# TV-B-Gone.net
KiCad netlist of a schematic drawn in EAGLE
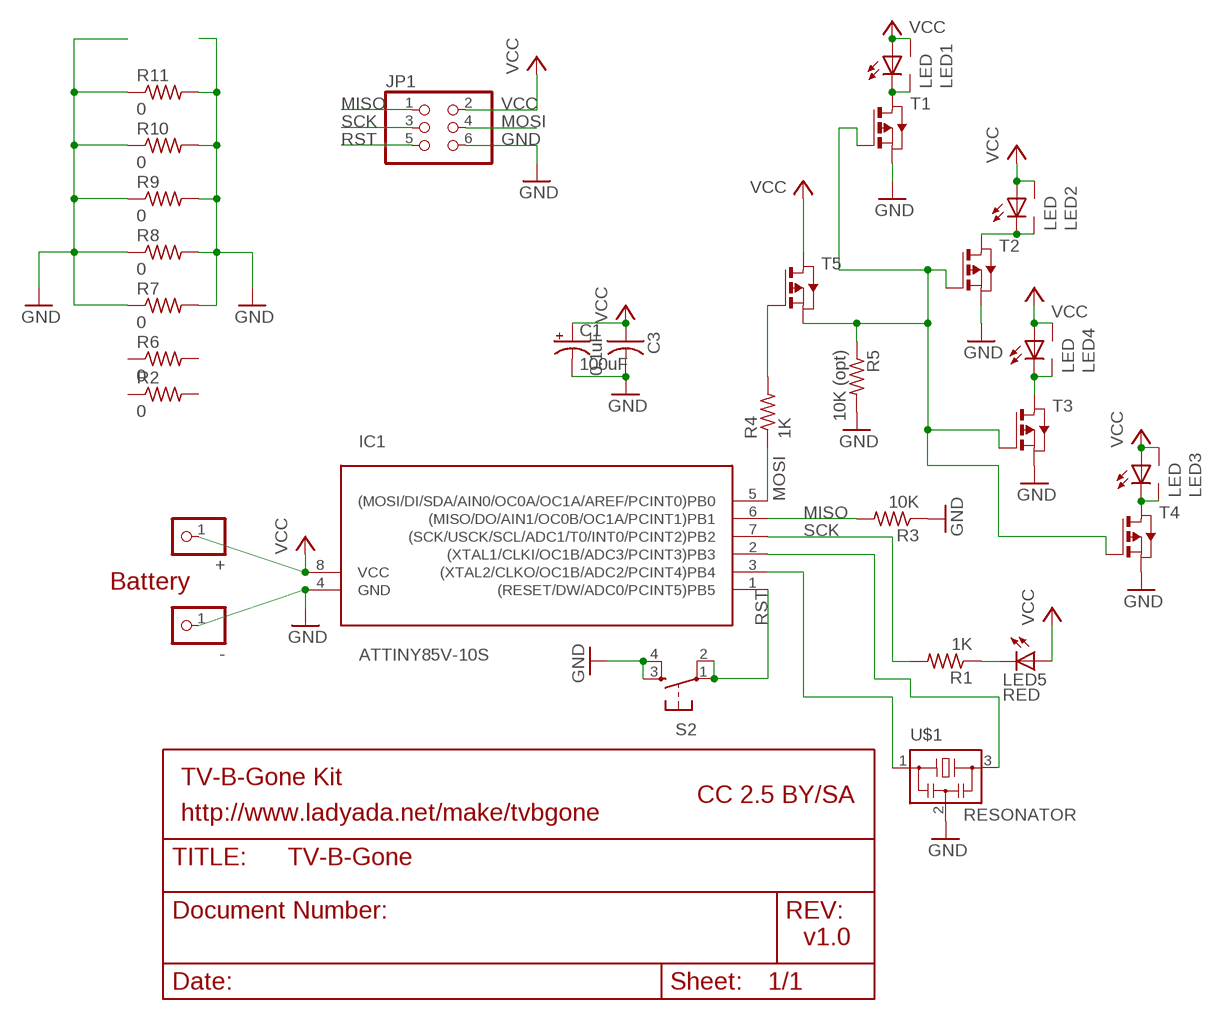
[diagram p0: schematic, sheet 1]

(export (version "E")
  (design (tool "Eeschema 10.0.6"))
  (components
    (comp (ref "+")
      (value "PINHD-1X1")
      (footprint "eagle-import:1X01")
      (libsource (lib "eagle-import") (part "PINHD-1X1"))
    )
    (comp (ref "-")
      (value "PINHD-1X1")
      (footprint "eagle-import:1X01")
      (libsource (lib "eagle-import") (part "PINHD-1X1"))
    )
    (comp (ref "C1")
      (value "100uF")
      (footprint "eagle-import:PANASONIC_E")
      (libsource (lib "eagle-import") (part "CAP_POLE"))
    )
    (comp (ref "C3")
      (value "0.1uF")
      (footprint "eagle-import:C1206FAB")
      (libsource (lib "eagle-import") (part "CAP-US1206FAB"))
    )
    (comp (ref "IC1")
      (value "ATTINY85V-10S")
      (footprint "eagle-import:SOIC8")
      (libsource (lib "eagle-import") (part "ATTINY85SV-10"))
    )
    (comp (ref "JP1")
      (value "PINHD-2X3-SMD")
      (footprint "eagle-import:2X03SMD")
      (libsource (lib "eagle-import") (part "PINHD-2X3-SMD"))
    )
    (comp (ref "LED1")
      (value "LED")
      (footprint "eagle-import:5MM-SIDE")
      (libsource (lib "eagle-import") (part "tvbgone_LED"))
    )
    (comp (ref "LED2")
      (value "LED")
      (footprint "eagle-import:5MM-SIDE")
      (libsource (lib "eagle-import") (part "tvbgone_LED"))
    )
    (comp (ref "LED3")
      (value "LED")
      (footprint "eagle-import:5MM-SIDE")
      (libsource (lib "eagle-import") (part "tvbgone_LED"))
    )
    (comp (ref "LED4")
      (value "LED")
      (footprint "eagle-import:5MM-SIDE")
      (libsource (lib "eagle-import") (part "tvbgone_LED"))
    )
    (comp (ref "LED5")
      (value "RED")
      (footprint "eagle-import:CHIPLED_1206")
      (libsource (lib "eagle-import") (part "LEDCHIPLED_1206"))
    )
    (comp (ref "R1")
      (value "1K")
      (footprint "eagle-import:R1206FAB")
      (libsource (lib "eagle-import") (part "RES-US1206FAB"))
    )
    (comp (ref "R2")
      (value "0")
      (footprint "eagle-import:R1206FAB")
      (libsource (lib "eagle-import") (part "RES-US1206FAB"))
    )
    (comp (ref "R3")
      (value "10K")
      (footprint "eagle-import:R1206FAB")
      (libsource (lib "eagle-import") (part "RES-US1206FAB"))
    )
    (comp (ref "R4")
      (value "1K")
      (footprint "eagle-import:R1206FAB")
      (libsource (lib "eagle-import") (part "RES-US1206FAB"))
    )
    (comp (ref "R5")
      (value "10K (opt)")
      (footprint "eagle-import:R1206FAB")
      (libsource (lib "eagle-import") (part "RES-US1206FAB"))
    )
    (comp (ref "R6")
      (value "0")
      (footprint "eagle-import:R1206FAB")
      (libsource (lib "eagle-import") (part "RES-US1206FAB"))
    )
    (comp (ref "R7")
      (value "0")
      (footprint "eagle-import:R1206FAB")
      (libsource (lib "eagle-import") (part "RES-US1206FAB"))
    )
    (comp (ref "R8")
      (value "0")
      (footprint "eagle-import:R1206FAB")
      (libsource (lib "eagle-import") (part "RES-US1206FAB"))
    )
    (comp (ref "R9")
      (value "0")
      (footprint "eagle-import:R1206FAB")
      (libsource (lib "eagle-import") (part "RES-US1206FAB"))
    )
    (comp (ref "R10")
      (value "0")
      (footprint "eagle-import:R1206FAB")
      (libsource (lib "eagle-import") (part "RES-US1206FAB"))
    )
    (comp (ref "R11")
      (value "0")
      (footprint "eagle-import:R1206FAB")
      (libsource (lib "eagle-import") (part "RES-US1206FAB"))
    )
    (comp (ref "S2")
      (value "6MM_SWITCH6MM_SWITCH")
      (footprint "eagle-import:6MM_SWITCH")
      (libsource (lib "eagle-import") (part "6MM_SWITCH6MM_SWITCH"))
    )
    (comp (ref "T1")
      (value "PMOSFETSOT23")
      (footprint "eagle-import:SOT-23")
      (libsource (lib "eagle-import") (part "PMOSFETSOT23"))
    )
    (comp (ref "T2")
      (value "PMOSFETSOT23")
      (footprint "eagle-import:SOT-23")
      (libsource (lib "eagle-import") (part "PMOSFETSOT23"))
    )
    (comp (ref "T3")
      (value "PMOSFETSOT23")
      (footprint "eagle-import:SOT-23")
      (libsource (lib "eagle-import") (part "PMOSFETSOT23"))
    )
    (comp (ref "T4")
      (value "PMOSFETSOT23")
      (footprint "eagle-import:SOT-23")
      (libsource (lib "eagle-import") (part "PMOSFETSOT23"))
    )
    (comp (ref "T5")
      (value "PMOSFETSOT23")
      (footprint "eagle-import:SOT-23")
      (libsource (lib "eagle-import") (part "PMOSFETSOT23"))
    )
    (comp (ref "U$1")
      (value "RESONATOR")
      (footprint "eagle-import:EFOBM")
      (libsource (lib "eagle-import") (part "RESONATOR"))
    )
  )
  (nets
    (net (code "1") (name "/MISO") (class "Default")
      (node (ref "IC1") (pin "6") (pinfunction "(MISO/DO/AIN1/OC0B/OC1A/PCINT1)PB1_6") (pintype "bidirectional"))
      (node (ref "JP1") (pin "1") (pinfunction "1_1") (pintype "passive"))
      (node (ref "R3") (pin "2") (pinfunction "2_2") (pintype "passive"))
    )
    (net (code "2") (name "/MOSI") (class "Default")
      (node (ref "IC1") (pin "5") (pinfunction "(MOSI/DI/SDA/AIN0/OC0A/OC1A/AREF/PCINT0)PB0_5") (pintype "bidirectional"))
      (node (ref "JP1") (pin "4") (pinfunction "4_4") (pintype "passive"))
      (node (ref "R4") (pin "1") (pinfunction "1_1") (pintype "passive"))
    )
    (net (code "3") (name "/RST") (class "Default")
      (node (ref "IC1") (pin "1") (pinfunction "(RESET/DW/ADC0/PCINT5)PB5_1") (pintype "bidirectional"))
      (node (ref "JP1") (pin "5") (pinfunction "5_5") (pintype "passive"))
      (node (ref "S2") (pin "1") (pinfunction "P_1") (pintype "passive"))
      (node (ref "S2") (pin "2") (pinfunction "P1_2") (pintype "passive"))
    )
    (net (code "4") (name "/SCK") (class "Default")
      (node (ref "IC1") (pin "7") (pinfunction "(SCK/USCK/SCL/ADC1/T0/INT0/PCINT2)PB2_7") (pintype "bidirectional"))
      (node (ref "JP1") (pin "3") (pinfunction "3_3") (pintype "passive"))
      (node (ref "R1") (pin "2") (pinfunction "2_2") (pintype "passive"))
    )
    (net (code "5") (name "GND") (class "Default")
      (node (ref "-") (pin "1") (pinfunction "1_1") (pintype "passive"))
      (node (ref "C1") (pin "-") (pinfunction "-_-") (pintype "passive"))
      (node (ref "C3") (pin "2") (pinfunction "2_2") (pintype "passive"))
      (node (ref "IC1") (pin "4") (pinfunction "GND_4") (pintype "bidirectional"))
      (node (ref "JP1") (pin "6") (pinfunction "6_6") (pintype "passive"))
      (node (ref "R10") (pin "1") (pinfunction "1_1") (pintype "passive"))
      (node (ref "R10") (pin "2") (pinfunction "2_2") (pintype "passive"))
      (node (ref "R11") (pin "1") (pinfunction "1_1") (pintype "passive"))
      (node (ref "R11") (pin "2") (pinfunction "2_2") (pintype "passive"))
      (node (ref "R3") (pin "1") (pinfunction "1_1") (pintype "passive"))
      (node (ref "R5") (pin "2") (pinfunction "2_2") (pintype "passive"))
      (node (ref "R7") (pin "1") (pinfunction "1_1") (pintype "passive"))
      (node (ref "R7") (pin "2") (pinfunction "2_2") (pintype "passive"))
      (node (ref "R8") (pin "1") (pinfunction "1_1") (pintype "passive"))
      (node (ref "R8") (pin "2") (pinfunction "2_2") (pintype "passive"))
      (node (ref "R9") (pin "1") (pinfunction "1_1") (pintype "passive"))
      (node (ref "R9") (pin "2") (pinfunction "2_2") (pintype "passive"))
      (node (ref "S2") (pin "3") (pinfunction "S_3") (pintype "passive"))
      (node (ref "S2") (pin "4") (pinfunction "S1_4") (pintype "passive"))
      (node (ref "T1") (pin "2") (pinfunction "S_2") (pintype "passive"))
      (node (ref "T2") (pin "2") (pinfunction "S_2") (pintype "passive"))
      (node (ref "T3") (pin "2") (pinfunction "S_2") (pintype "passive"))
      (node (ref "T4") (pin "2") (pinfunction "S_2") (pintype "passive"))
      (node (ref "U$1") (pin "2") (pinfunction "2_2") (pintype "passive"))
    )
    (net (code "6") (name "Net-(IC1-(XTAL1{slash}CLKI{slash}OC1B{slash}ADC3{slash}PCINT3)PB3)") (class "Default")
      (node (ref "IC1") (pin "2") (pinfunction "(XTAL1/CLKI/OC1B/ADC3/PCINT3)PB3_2") (pintype "bidirectional"))
      (node (ref "U$1") (pin "3") (pinfunction "3_3") (pintype "passive"))
    )
    (net (code "7") (name "Net-(IC1-(XTAL2{slash}CLKO{slash}OC1B{slash}ADC2{slash}PCINT4)PB4)") (class "Default")
      (node (ref "IC1") (pin "3") (pinfunction "(XTAL2/CLKO/OC1B/ADC2/PCINT4)PB4_3") (pintype "bidirectional"))
      (node (ref "U$1") (pin "1") (pinfunction "1_1") (pintype "passive"))
    )
    (net (code "8") (name "Net-(LED1-C)") (class "Default")
      (node (ref "LED1") (pin "K") (pinfunction "C_K") (pintype "passive"))
      (node (ref "LED1") (pin "K2") (pinfunction "C1_K2") (pintype "passive"))
      (node (ref "T1") (pin "1") (pinfunction "D_1") (pintype "passive"))
    )
    (net (code "9") (name "Net-(LED2-C)") (class "Default")
      (node (ref "LED2") (pin "K") (pinfunction "C_K") (pintype "passive"))
      (node (ref "LED2") (pin "K2") (pinfunction "C1_K2") (pintype "passive"))
      (node (ref "T2") (pin "1") (pinfunction "D_1") (pintype "passive"))
    )
    (net (code "10") (name "Net-(LED3-C)") (class "Default")
      (node (ref "LED3") (pin "K") (pinfunction "C_K") (pintype "passive"))
      (node (ref "LED3") (pin "K2") (pinfunction "C1_K2") (pintype "passive"))
      (node (ref "T4") (pin "1") (pinfunction "D_1") (pintype "passive"))
    )
    (net (code "11") (name "Net-(LED4-C)") (class "Default")
      (node (ref "LED4") (pin "K") (pinfunction "C_K") (pintype "passive"))
      (node (ref "LED4") (pin "K2") (pinfunction "C1_K2") (pintype "passive"))
      (node (ref "T3") (pin "1") (pinfunction "D_1") (pintype "passive"))
    )
    (net (code "12") (name "Net-(LED5-PadC)") (class "Default")
      (node (ref "LED5") (pin "C") (pinfunction "C_C") (pintype "passive"))
      (node (ref "R1") (pin "1") (pinfunction "1_1") (pintype "passive"))
    )
    (net (code "13") (name "Net-(T1-G)") (class "Default")
      (node (ref "R5") (pin "1") (pinfunction "1_1") (pintype "passive"))
      (node (ref "T1") (pin "3") (pinfunction "G_3") (pintype "passive"))
      (node (ref "T2") (pin "3") (pinfunction "G_3") (pintype "passive"))
      (node (ref "T3") (pin "3") (pinfunction "G_3") (pintype "passive"))
      (node (ref "T4") (pin "3") (pinfunction "G_3") (pintype "passive"))
      (node (ref "T5") (pin "2") (pinfunction "S_2") (pintype "passive"))
    )
    (net (code "14") (name "Net-(T5-G)") (class "Default")
      (node (ref "R4") (pin "2") (pinfunction "2_2") (pintype "passive"))
      (node (ref "T5") (pin "3") (pinfunction "G_3") (pintype "passive"))
    )
    (net (code "15") (name "VCC") (class "Default")
      (node (ref "+") (pin "1") (pinfunction "1_1") (pintype "passive"))
      (node (ref "C1") (pin "+") (pinfunction "+_+") (pintype "passive"))
      (node (ref "C3") (pin "1") (pinfunction "1_1") (pintype "passive"))
      (node (ref "IC1") (pin "8") (pinfunction "VCC_8") (pintype "bidirectional"))
      (node (ref "JP1") (pin "2") (pinfunction "2_2") (pintype "passive"))
      (node (ref "LED1") (pin "A") (pinfunction "A_A") (pintype "passive"))
      (node (ref "LED1") (pin "A2") (pinfunction "A1_A2") (pintype "passive"))
      (node (ref "LED2") (pin "A") (pinfunction "A_A") (pintype "passive"))
      (node (ref "LED2") (pin "A2") (pinfunction "A1_A2") (pintype "passive"))
      (node (ref "LED3") (pin "A") (pinfunction "A_A") (pintype "passive"))
      (node (ref "LED3") (pin "A2") (pinfunction "A1_A2") (pintype "passive"))
      (node (ref "LED4") (pin "A") (pinfunction "A_A") (pintype "passive"))
      (node (ref "LED4") (pin "A2") (pinfunction "A1_A2") (pintype "passive"))
      (node (ref "LED5") (pin "A") (pinfunction "A_A") (pintype "passive"))
      (node (ref "T5") (pin "1") (pinfunction "D_1") (pintype "passive"))
    )
    (net (code "16") (name "unconnected-(R2-Pad1)") (class "Default")
      (node (ref "R2") (pin "1") (pinfunction "1_1") (pintype "passive"))
    )
    (net (code "17") (name "unconnected-(R2-Pad2)") (class "Default")
      (node (ref "R2") (pin "2") (pinfunction "2_2") (pintype "passive"))
    )
    (net (code "18") (name "unconnected-(R6-Pad1)") (class "Default")
      (node (ref "R6") (pin "1") (pinfunction "1_1") (pintype "passive"))
    )
    (net (code "19") (name "unconnected-(R6-Pad2)") (class "Default")
      (node (ref "R6") (pin "2") (pinfunction "2_2") (pintype "passive"))
    )
  )
)
